# mainBoard.net
KiCad netlist of a schematic drawn in EAGLE
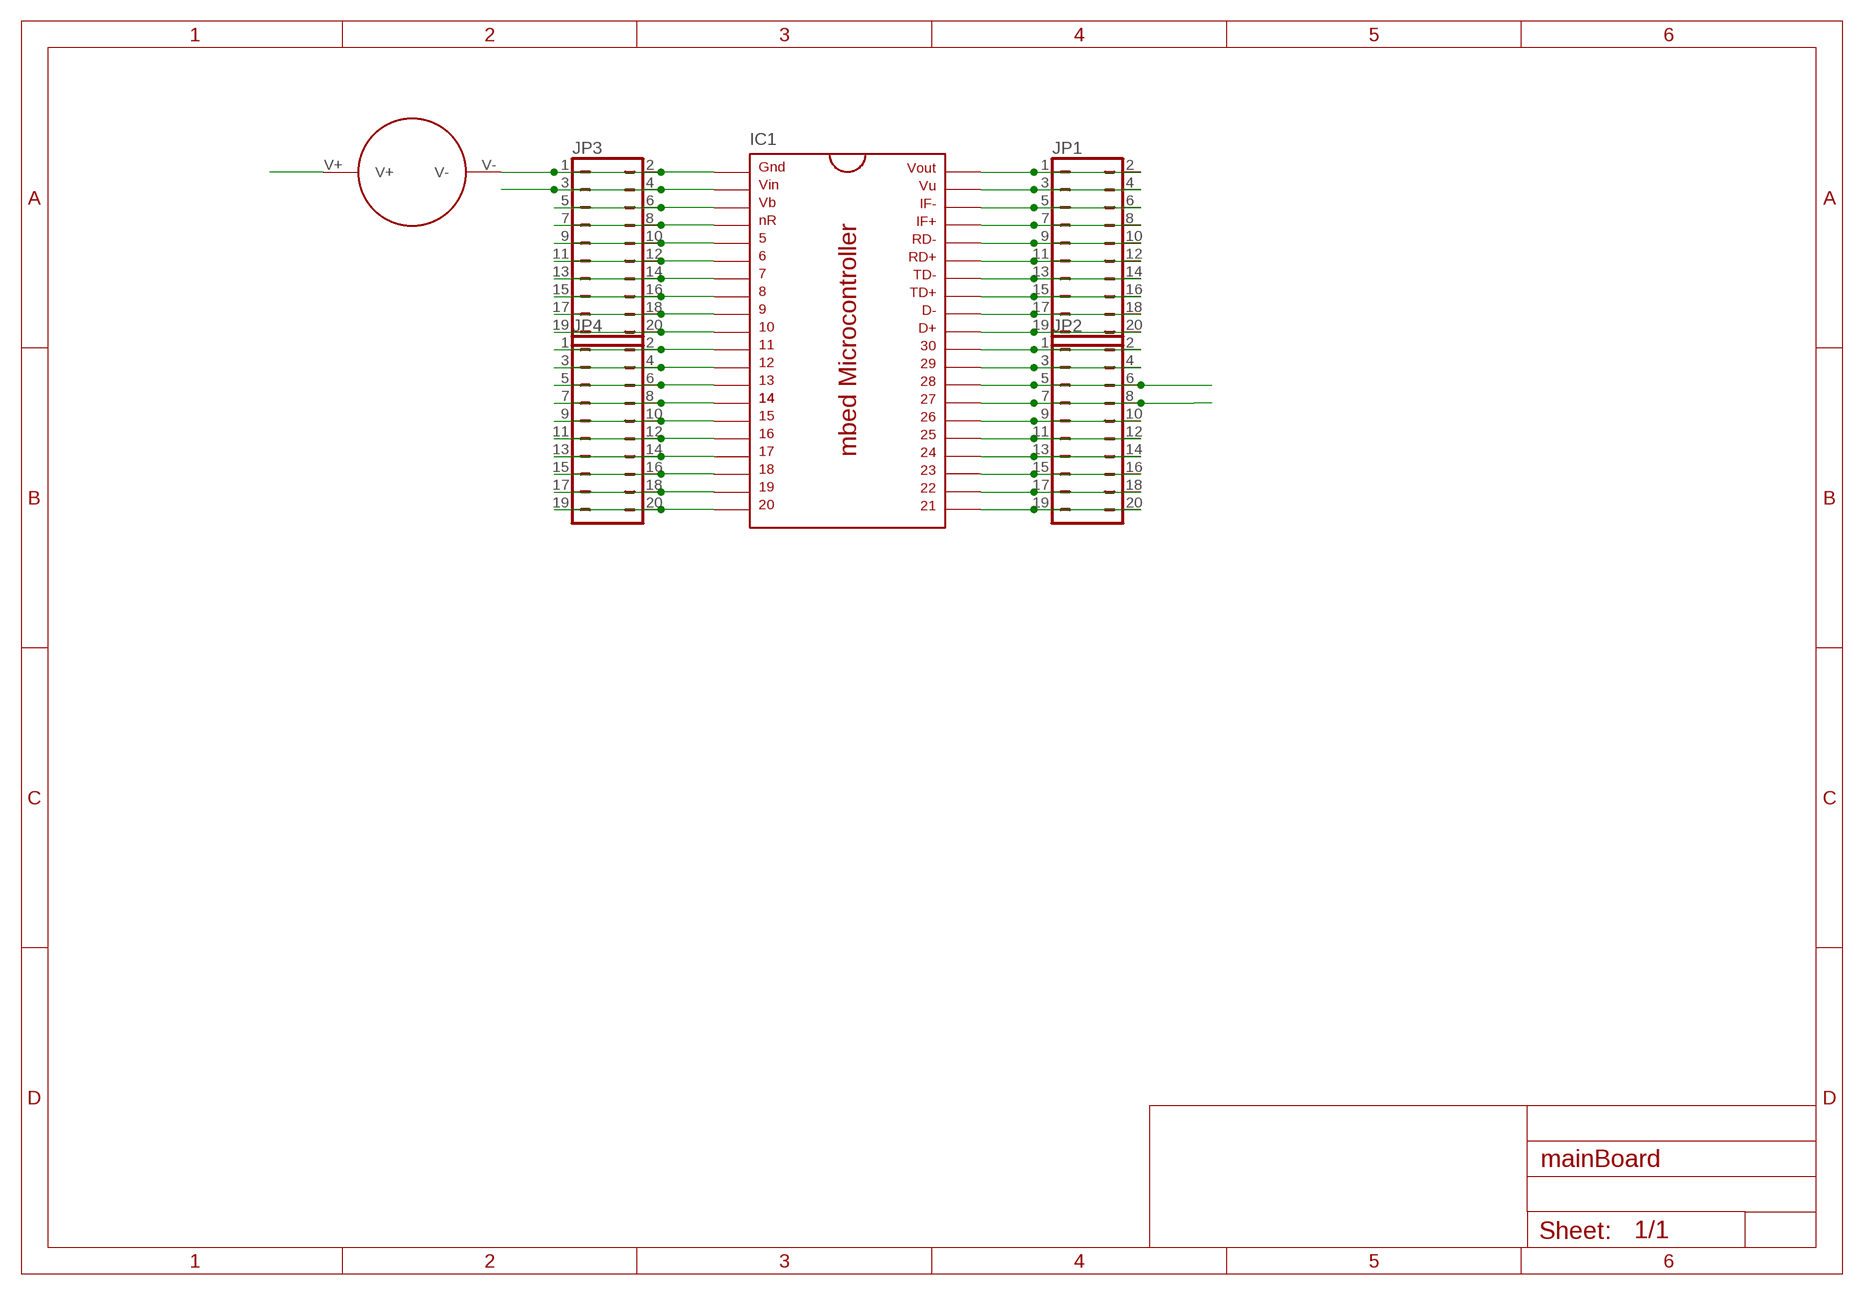
[diagram p0: schematic, sheet 1]

(export (version "E")
  (design (tool "Eeschema 10.0.6"))
  (components
    (comp (ref "IC1")
      (value "MBED_MICROCONTROLLER")
      (footprint "eagle-import:DIL40_0.9")
      (libsource (lib "eagle-import") (part "MBED_MICROCONTROLLER"))
    )
    (comp (ref "JP1")
      (value "JP10Q")
      (footprint "eagle-import:JP10Q")
      (libsource (lib "eagle-import") (part "JP10Q"))
    )
    (comp (ref "JP2")
      (value "JP10Q")
      (footprint "eagle-import:JP10Q")
      (libsource (lib "eagle-import") (part "JP10Q"))
    )
    (comp (ref "JP3")
      (value "JP10Q")
      (footprint "eagle-import:JP10Q")
      (libsource (lib "eagle-import") (part "JP10Q"))
    )
    (comp (ref "JP4")
      (value "JP10Q")
      (footprint "eagle-import:JP10Q")
      (libsource (lib "eagle-import") (part "JP10Q"))
    )
    (comp (ref "U$1")
      (value "PANASONIC_BATTERYTHROUGH_HOLE")
      (footprint "eagle-import:PANASONIC_BATTERY")
      (libsource (lib "eagle-import") (part "PANASONIC_BATTERYTHROUGH_HOLE"))
    )
  )
  (nets
    (net (code "1") (name "/VB") (class "Default")
      (node (ref "IC1") (pin "3") (pinfunction "P$3_3") (pintype "bidirectional"))
      (node (ref "JP3") (pin "5") (pinfunction "5_5") (pintype "passive"))
      (node (ref "JP3") (pin "6") (pinfunction "6_6") (pintype "passive"))
      (node (ref "U$1") (pin "V+") (pinfunction "V+_V+") (pintype "bidirectional"))
    )
    (net (code "2") (name "Net-(IC1-P$1)") (class "Default")
      (node (ref "IC1") (pin "1") (pinfunction "P$1_1") (pintype "bidirectional"))
      (node (ref "JP3") (pin "1") (pinfunction "1_1") (pintype "passive"))
      (node (ref "JP3") (pin "2") (pinfunction "2_2") (pintype "passive"))
      (node (ref "U$1") (pin "V-") (pinfunction "V-_V-") (pintype "bidirectional"))
    )
    (net (code "3") (name "Net-(IC1-P$2)") (class "Default")
      (node (ref "IC1") (pin "2") (pinfunction "P$2_2") (pintype "bidirectional"))
      (node (ref "JP3") (pin "3") (pinfunction "3_3") (pintype "passive"))
      (node (ref "JP3") (pin "4") (pinfunction "4_4") (pintype "passive"))
    )
    (net (code "4") (name "Net-(IC1-P$4)") (class "Default")
      (node (ref "IC1") (pin "4") (pinfunction "P$4_4") (pintype "bidirectional"))
      (node (ref "JP3") (pin "7") (pinfunction "7_7") (pintype "passive"))
      (node (ref "JP3") (pin "8") (pinfunction "8_8") (pintype "passive"))
    )
    (net (code "5") (name "Net-(IC1-P$5)") (class "Default")
      (node (ref "IC1") (pin "5") (pinfunction "P$5_5") (pintype "bidirectional"))
      (node (ref "JP3") (pin "10") (pinfunction "10_10") (pintype "passive"))
      (node (ref "JP3") (pin "9") (pinfunction "9_9") (pintype "passive"))
    )
    (net (code "6") (name "Net-(IC1-P$6)") (class "Default")
      (node (ref "IC1") (pin "6") (pinfunction "P$6_6") (pintype "bidirectional"))
      (node (ref "JP3") (pin "11") (pinfunction "11_11") (pintype "passive"))
      (node (ref "JP3") (pin "12") (pinfunction "12_12") (pintype "passive"))
    )
    (net (code "7") (name "Net-(IC1-P$7)") (class "Default")
      (node (ref "IC1") (pin "7") (pinfunction "P$7_7") (pintype "bidirectional"))
      (node (ref "JP3") (pin "13") (pinfunction "13_13") (pintype "passive"))
      (node (ref "JP3") (pin "14") (pinfunction "14_14") (pintype "passive"))
    )
    (net (code "8") (name "Net-(IC1-P$8)") (class "Default")
      (node (ref "IC1") (pin "8") (pinfunction "P$8_8") (pintype "bidirectional"))
      (node (ref "JP3") (pin "15") (pinfunction "15_15") (pintype "passive"))
      (node (ref "JP3") (pin "16") (pinfunction "16_16") (pintype "passive"))
    )
    (net (code "9") (name "Net-(IC1-P$9)") (class "Default")
      (node (ref "IC1") (pin "9") (pinfunction "P$9_9") (pintype "bidirectional"))
      (node (ref "JP3") (pin "17") (pinfunction "17_17") (pintype "passive"))
      (node (ref "JP3") (pin "18") (pinfunction "18_18") (pintype "passive"))
    )
    (net (code "10") (name "Net-(IC1-P$10)") (class "Default")
      (node (ref "IC1") (pin "10") (pinfunction "P$10_10") (pintype "bidirectional"))
      (node (ref "JP3") (pin "19") (pinfunction "19_19") (pintype "passive"))
      (node (ref "JP3") (pin "20") (pinfunction "20_20") (pintype "passive"))
    )
    (net (code "11") (name "Net-(IC1-P$11)") (class "Default")
      (node (ref "IC1") (pin "11") (pinfunction "P$11_11") (pintype "bidirectional"))
      (node (ref "JP4") (pin "1") (pinfunction "1_1") (pintype "passive"))
      (node (ref "JP4") (pin "2") (pinfunction "2_2") (pintype "passive"))
    )
    (net (code "12") (name "Net-(IC1-P$12)") (class "Default")
      (node (ref "IC1") (pin "12") (pinfunction "P$12_12") (pintype "bidirectional"))
      (node (ref "JP4") (pin "3") (pinfunction "3_3") (pintype "passive"))
      (node (ref "JP4") (pin "4") (pinfunction "4_4") (pintype "passive"))
    )
    (net (code "13") (name "Net-(IC1-P$13)") (class "Default")
      (node (ref "IC1") (pin "13") (pinfunction "P$13_13") (pintype "bidirectional"))
      (node (ref "JP4") (pin "5") (pinfunction "5_5") (pintype "passive"))
      (node (ref "JP4") (pin "6") (pinfunction "6_6") (pintype "passive"))
    )
    (net (code "14") (name "Net-(IC1-P$14)") (class "Default")
      (node (ref "IC1") (pin "14") (pinfunction "P$14_14") (pintype "bidirectional"))
      (node (ref "JP4") (pin "7") (pinfunction "7_7") (pintype "passive"))
      (node (ref "JP4") (pin "8") (pinfunction "8_8") (pintype "passive"))
    )
    (net (code "15") (name "Net-(IC1-P$15)") (class "Default")
      (node (ref "IC1") (pin "15") (pinfunction "P$15_15") (pintype "bidirectional"))
      (node (ref "JP4") (pin "10") (pinfunction "10_10") (pintype "passive"))
      (node (ref "JP4") (pin "9") (pinfunction "9_9") (pintype "passive"))
    )
    (net (code "16") (name "Net-(IC1-P$16)") (class "Default")
      (node (ref "IC1") (pin "16") (pinfunction "P$16_16") (pintype "bidirectional"))
      (node (ref "JP4") (pin "11") (pinfunction "11_11") (pintype "passive"))
      (node (ref "JP4") (pin "12") (pinfunction "12_12") (pintype "passive"))
    )
    (net (code "17") (name "Net-(IC1-P$17)") (class "Default")
      (node (ref "IC1") (pin "17") (pinfunction "P$17_17") (pintype "bidirectional"))
      (node (ref "JP4") (pin "13") (pinfunction "13_13") (pintype "passive"))
      (node (ref "JP4") (pin "14") (pinfunction "14_14") (pintype "passive"))
    )
    (net (code "18") (name "Net-(IC1-P$18)") (class "Default")
      (node (ref "IC1") (pin "18") (pinfunction "P$18_18") (pintype "bidirectional"))
      (node (ref "JP4") (pin "15") (pinfunction "15_15") (pintype "passive"))
      (node (ref "JP4") (pin "16") (pinfunction "16_16") (pintype "passive"))
    )
    (net (code "19") (name "Net-(IC1-P$19)") (class "Default")
      (node (ref "IC1") (pin "19") (pinfunction "P$19_19") (pintype "bidirectional"))
      (node (ref "JP4") (pin "17") (pinfunction "17_17") (pintype "passive"))
      (node (ref "JP4") (pin "18") (pinfunction "18_18") (pintype "passive"))
    )
    (net (code "20") (name "Net-(IC1-P$20)") (class "Default")
      (node (ref "IC1") (pin "20") (pinfunction "P$20_20") (pintype "bidirectional"))
      (node (ref "JP4") (pin "19") (pinfunction "19_19") (pintype "passive"))
      (node (ref "JP4") (pin "20") (pinfunction "20_20") (pintype "passive"))
    )
    (net (code "21") (name "Net-(IC1-P$21)") (class "Default")
      (node (ref "IC1") (pin "21") (pinfunction "P$21_21") (pintype "bidirectional"))
      (node (ref "JP2") (pin "19") (pinfunction "19_19") (pintype "passive"))
      (node (ref "JP2") (pin "20") (pinfunction "20_20") (pintype "passive"))
    )
    (net (code "22") (name "Net-(IC1-P$22)") (class "Default")
      (node (ref "IC1") (pin "22") (pinfunction "P$22_22") (pintype "bidirectional"))
      (node (ref "JP2") (pin "17") (pinfunction "17_17") (pintype "passive"))
      (node (ref "JP2") (pin "18") (pinfunction "18_18") (pintype "passive"))
    )
    (net (code "23") (name "Net-(IC1-P$23)") (class "Default")
      (node (ref "IC1") (pin "23") (pinfunction "P$23_23") (pintype "bidirectional"))
      (node (ref "JP2") (pin "15") (pinfunction "15_15") (pintype "passive"))
      (node (ref "JP2") (pin "16") (pinfunction "16_16") (pintype "passive"))
    )
    (net (code "24") (name "Net-(IC1-P$24)") (class "Default")
      (node (ref "IC1") (pin "24") (pinfunction "P$24_24") (pintype "bidirectional"))
      (node (ref "JP2") (pin "13") (pinfunction "13_13") (pintype "passive"))
      (node (ref "JP2") (pin "14") (pinfunction "14_14") (pintype "passive"))
    )
    (net (code "25") (name "Net-(IC1-P$25)") (class "Default")
      (node (ref "IC1") (pin "25") (pinfunction "P$25_25") (pintype "bidirectional"))
      (node (ref "JP2") (pin "11") (pinfunction "11_11") (pintype "passive"))
      (node (ref "JP2") (pin "12") (pinfunction "12_12") (pintype "passive"))
    )
    (net (code "26") (name "Net-(IC1-P$26)") (class "Default")
      (node (ref "IC1") (pin "26") (pinfunction "P$26_26") (pintype "bidirectional"))
      (node (ref "JP2") (pin "10") (pinfunction "10_10") (pintype "passive"))
      (node (ref "JP2") (pin "9") (pinfunction "9_9") (pintype "passive"))
    )
    (net (code "27") (name "Net-(IC1-P$27)") (class "Default")
      (node (ref "IC1") (pin "27") (pinfunction "P$27_27") (pintype "bidirectional"))
      (node (ref "JP2") (pin "7") (pinfunction "7_7") (pintype "passive"))
      (node (ref "JP2") (pin "8") (pinfunction "8_8") (pintype "passive"))
    )
    (net (code "28") (name "Net-(IC1-P$28)") (class "Default")
      (node (ref "IC1") (pin "28") (pinfunction "P$28_28") (pintype "bidirectional"))
      (node (ref "JP2") (pin "5") (pinfunction "5_5") (pintype "passive"))
      (node (ref "JP2") (pin "6") (pinfunction "6_6") (pintype "passive"))
    )
    (net (code "29") (name "Net-(IC1-P$29)") (class "Default")
      (node (ref "IC1") (pin "29") (pinfunction "P$29_29") (pintype "bidirectional"))
      (node (ref "JP2") (pin "3") (pinfunction "3_3") (pintype "passive"))
      (node (ref "JP2") (pin "4") (pinfunction "4_4") (pintype "passive"))
    )
    (net (code "30") (name "Net-(IC1-P$30)") (class "Default")
      (node (ref "IC1") (pin "30") (pinfunction "P$30_30") (pintype "bidirectional"))
      (node (ref "JP2") (pin "1") (pinfunction "1_1") (pintype "passive"))
      (node (ref "JP2") (pin "2") (pinfunction "2_2") (pintype "passive"))
    )
    (net (code "31") (name "Net-(IC1-P$31)") (class "Default")
      (node (ref "IC1") (pin "31") (pinfunction "P$31_31") (pintype "bidirectional"))
      (node (ref "JP1") (pin "19") (pinfunction "19_19") (pintype "passive"))
      (node (ref "JP1") (pin "20") (pinfunction "20_20") (pintype "passive"))
    )
    (net (code "32") (name "Net-(IC1-P$32)") (class "Default")
      (node (ref "IC1") (pin "32") (pinfunction "P$32_32") (pintype "bidirectional"))
      (node (ref "JP1") (pin "17") (pinfunction "17_17") (pintype "passive"))
      (node (ref "JP1") (pin "18") (pinfunction "18_18") (pintype "passive"))
    )
    (net (code "33") (name "Net-(IC1-P$33)") (class "Default")
      (node (ref "IC1") (pin "33") (pinfunction "P$33_33") (pintype "bidirectional"))
      (node (ref "JP1") (pin "15") (pinfunction "15_15") (pintype "passive"))
      (node (ref "JP1") (pin "16") (pinfunction "16_16") (pintype "passive"))
    )
    (net (code "34") (name "Net-(IC1-P$34)") (class "Default")
      (node (ref "IC1") (pin "34") (pinfunction "P$34_34") (pintype "bidirectional"))
      (node (ref "JP1") (pin "13") (pinfunction "13_13") (pintype "passive"))
      (node (ref "JP1") (pin "14") (pinfunction "14_14") (pintype "passive"))
    )
    (net (code "35") (name "Net-(IC1-P$35)") (class "Default")
      (node (ref "IC1") (pin "35") (pinfunction "P$35_35") (pintype "bidirectional"))
      (node (ref "JP1") (pin "11") (pinfunction "11_11") (pintype "passive"))
      (node (ref "JP1") (pin "12") (pinfunction "12_12") (pintype "passive"))
    )
    (net (code "36") (name "Net-(IC1-P$36)") (class "Default")
      (node (ref "IC1") (pin "36") (pinfunction "P$36_36") (pintype "bidirectional"))
      (node (ref "JP1") (pin "10") (pinfunction "10_10") (pintype "passive"))
      (node (ref "JP1") (pin "9") (pinfunction "9_9") (pintype "passive"))
    )
    (net (code "37") (name "Net-(IC1-P$37)") (class "Default")
      (node (ref "IC1") (pin "37") (pinfunction "P$37_37") (pintype "bidirectional"))
      (node (ref "JP1") (pin "7") (pinfunction "7_7") (pintype "passive"))
      (node (ref "JP1") (pin "8") (pinfunction "8_8") (pintype "passive"))
    )
    (net (code "38") (name "Net-(IC1-P$38)") (class "Default")
      (node (ref "IC1") (pin "38") (pinfunction "P$38_38") (pintype "bidirectional"))
      (node (ref "JP1") (pin "5") (pinfunction "5_5") (pintype "passive"))
      (node (ref "JP1") (pin "6") (pinfunction "6_6") (pintype "passive"))
    )
    (net (code "39") (name "Net-(IC1-P$39)") (class "Default")
      (node (ref "IC1") (pin "39") (pinfunction "P$39_39") (pintype "bidirectional"))
      (node (ref "JP1") (pin "3") (pinfunction "3_3") (pintype "passive"))
      (node (ref "JP1") (pin "4") (pinfunction "4_4") (pintype "passive"))
    )
    (net (code "40") (name "Net-(IC1-P$40)") (class "Default")
      (node (ref "IC1") (pin "40") (pinfunction "P$40_40") (pintype "bidirectional"))
      (node (ref "JP1") (pin "1") (pinfunction "1_1") (pintype "passive"))
      (node (ref "JP1") (pin "2") (pinfunction "2_2") (pintype "passive"))
    )
  )
)
